# OPA847.net
KiCad netlist of a schematic drawn in Altium Designer
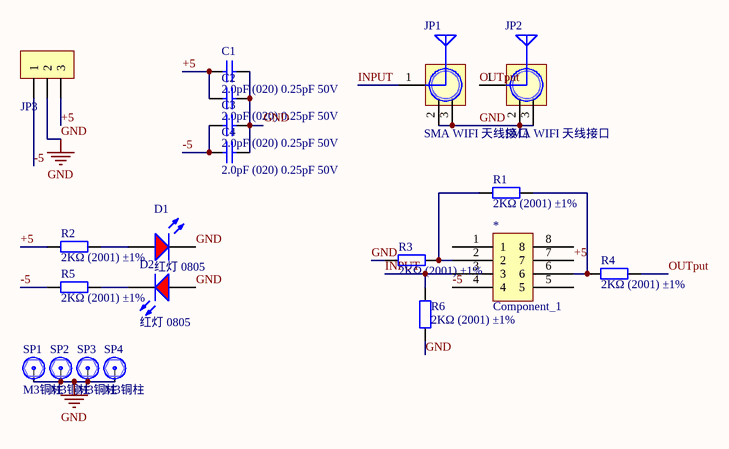
[diagram p0: OPA847.SchDoc]

(export (version "E")
  (design (tool "Eeschema 10.0.6"))
  (components
    (comp (ref "*")
      (value "Component_1")
      (footprint "SOP8_N")
      (libsource (lib "Schlib1") (part "Component_1"))
    )
    (comp (ref "C1")
      (value "2.0pF (020) 0.25pF 50V")
      (footprint "0603_C")
      (description "贴片电容")
      (libsource (lib "Miscellaneous Devices LC") (part "0603 2.0pF (020) 0.25pF 50V"))
    )
    (comp (ref "C2")
      (value "2.0pF (020) 0.25pF 50V")
      (footprint "0603_C")
      (description "贴片电容")
      (libsource (lib "Miscellaneous Devices LC") (part "0603 2.0pF (020) 0.25pF 50V"))
    )
    (comp (ref "C3")
      (value "2.0pF (020) 0.25pF 50V")
      (footprint "0603_C")
      (description "贴片电容")
      (libsource (lib "Miscellaneous Devices LC") (part "0603 2.0pF (020) 0.25pF 50V"))
    )
    (comp (ref "C4")
      (value "2.0pF (020) 0.25pF 50V")
      (footprint "0603_C")
      (description "贴片电容")
      (libsource (lib "Miscellaneous Devices LC") (part "0603 2.0pF (020) 0.25pF 50V"))
    )
    (comp (ref "D1")
      (value "红灯 0805")
      (footprint "0805_LED_S1")
      (description "发光二极管")
      (libsource (lib "Miscellaneous Devices LC") (part "0805 红灯"))
    )
    (comp (ref "D2")
      (value "红灯 0805")
      (footprint "0805_LED_S1")
      (description "发光二极管")
      (libsource (lib "Miscellaneous Devices LC") (part "0805 红灯"))
    )
    (comp (ref "JP1")
      (value "SMA WIFI 天线接口")
      (footprint "SMA-KE")
      (description "SMA-2.4G射频天线接口")
      (libsource (lib "天线") (part "SMA"))
    )
    (comp (ref "JP2")
      (value "SMA WIFI 天线接口")
      (footprint "SMA-KE")
      (description "SMA-2.4G射频天线接口")
      (libsource (lib "天线") (part "SMA"))
    )
    (comp (ref "JP3")
      (value "HDR-1X3")
      (footprint "XH2.54-WI-3P")
      (description "3P接插件")
      (libsource (lib "XH2.54") (part "Header 3"))
    )
    (comp (ref "R1")
      (value "2KΩ (2001) ±1%")
      (footprint "0805_R")
      (description "贴片电阻")
      (libsource (lib "Miscellaneous Devices LC") (part "0805 2KΩ (2001) 1%"))
    )
    (comp (ref "R2")
      (value "2KΩ (2001) ±1%")
      (footprint "0805_R")
      (description "贴片电阻")
      (libsource (lib "Miscellaneous Devices LC") (part "0805 2KΩ (2001) 1%"))
    )
    (comp (ref "R3")
      (value "2KΩ (2001) ±1%")
      (footprint "0805_R")
      (description "贴片电阻")
      (libsource (lib "Miscellaneous Devices LC") (part "0805 2KΩ (2001) 1%"))
    )
    (comp (ref "R4")
      (value "2KΩ (2001) ±1%")
      (footprint "0805_R")
      (description "贴片电阻")
      (libsource (lib "Miscellaneous Devices LC") (part "0805 2KΩ (2001) 1%"))
    )
    (comp (ref "R5")
      (value "2KΩ (2001) ±1%")
      (footprint "0805_R")
      (description "贴片电阻")
      (libsource (lib "Miscellaneous Devices LC") (part "0805 2KΩ (2001) 1%"))
    )
    (comp (ref "R6")
      (value "2KΩ (2001) ±1%")
      (footprint "0805_R")
      (description "贴片电阻")
      (libsource (lib "") (part "0805 2KΩ (2001) 1%_1"))
    )
    (comp (ref "SP1")
      (value "M3铜柱")
      (footprint "M3x4_L")
      (description "铜柱")
      (libsource (lib "铜柱-测试点-电池座-蜂鸣器") (part "铜柱小焊盘"))
    )
    (comp (ref "SP2")
      (value "M3铜柱")
      (footprint "M3x4_L")
      (description "铜柱")
      (libsource (lib "铜柱-测试点-电池座-蜂鸣器") (part "铜柱小焊盘"))
    )
    (comp (ref "SP3")
      (value "M3铜柱")
      (footprint "M3x4_L")
      (description "铜柱")
      (libsource (lib "铜柱-测试点-电池座-蜂鸣器") (part "铜柱小焊盘"))
    )
    (comp (ref "SP4")
      (value "M3铜柱")
      (footprint "M3x4_L")
      (description "铜柱")
      (libsource (lib "铜柱-测试点-电池座-蜂鸣器") (part "铜柱小焊盘"))
    )
  )
  (nets
    (net (code "1") (name "/+5") (class "Default")
      (node (ref "*") (pin "7") (pinfunction "7_7") (pintype "passive"))
      (node (ref "C1") (pin "1") (pinfunction "1_1") (pintype "passive"))
      (node (ref "C2") (pin "1") (pinfunction "1_1") (pintype "passive"))
      (node (ref "JP3") (pin "3") (pinfunction "3_3") (pintype "passive"))
      (node (ref "R2") (pin "1") (pinfunction "1_1") (pintype "passive"))
    )
    (net (code "2") (name "/-5") (class "Default")
      (node (ref "*") (pin "4") (pinfunction "4_4") (pintype "passive"))
      (node (ref "C3") (pin "1") (pinfunction "1_1") (pintype "passive"))
      (node (ref "C4") (pin "1") (pinfunction "1_1") (pintype "passive"))
      (node (ref "JP3") (pin "1") (pinfunction "1_1") (pintype "passive"))
      (node (ref "R5") (pin "1") (pinfunction "1_1") (pintype "passive"))
    )
    (net (code "3") (name "/INPUT") (class "Default")
      (node (ref "*") (pin "3") (pinfunction "3_3") (pintype "passive"))
      (node (ref "JP1") (pin "1") (pinfunction "ANT_1") (pintype "passive"))
      (node (ref "R6") (pin "2") (pinfunction "2_2") (pintype "passive"))
    )
    (net (code "4") (name "/OUTput") (class "Default")
      (node (ref "JP2") (pin "1") (pinfunction "ANT_1") (pintype "passive"))
      (node (ref "R4") (pin "2") (pinfunction "2_2") (pintype "passive"))
    )
    (net (code "5") (name "GND") (class "Default")
      (node (ref "C1") (pin "2") (pinfunction "2_2") (pintype "passive"))
      (node (ref "C2") (pin "2") (pinfunction "2_2") (pintype "passive"))
      (node (ref "C3") (pin "2") (pinfunction "2_2") (pintype "passive"))
      (node (ref "C4") (pin "2") (pinfunction "2_2") (pintype "passive"))
      (node (ref "D1") (pin "K") (pinfunction "K_K") (pintype "passive"))
      (node (ref "D2") (pin "A") (pinfunction "A_A") (pintype "passive"))
      (node (ref "JP1") (pin "2") (pinfunction "GND_2") (pintype "passive"))
      (node (ref "JP1") (pin "3") (pinfunction "GND_3") (pintype "passive"))
      (node (ref "JP2") (pin "2") (pinfunction "GND_2") (pintype "passive"))
      (node (ref "JP2") (pin "3") (pinfunction "GND_3") (pintype "passive"))
      (node (ref "JP3") (pin "2") (pinfunction "2_2") (pintype "passive"))
      (node (ref "R3") (pin "1") (pinfunction "1_1") (pintype "passive"))
      (node (ref "R6") (pin "1") (pinfunction "1_1") (pintype "passive"))
      (node (ref "SP1") (pin "1") (pinfunction "1_1") (pintype "passive"))
      (node (ref "SP2") (pin "1") (pinfunction "1_1") (pintype "passive"))
      (node (ref "SP3") (pin "1") (pinfunction "1_1") (pintype "passive"))
      (node (ref "SP4") (pin "1") (pinfunction "1_1") (pintype "passive"))
    )
    (net (code "6") (name "Net-(*-Pad2)") (class "Default")
      (node (ref "*") (pin "2") (pinfunction "2_2") (pintype "passive"))
      (node (ref "R1") (pin "1") (pinfunction "1_1") (pintype "passive"))
      (node (ref "R3") (pin "2") (pinfunction "2_2") (pintype "passive"))
    )
    (net (code "7") (name "Net-(*-Pad6)") (class "Default")
      (node (ref "*") (pin "6") (pinfunction "6_6") (pintype "passive"))
      (node (ref "R1") (pin "2") (pinfunction "2_2") (pintype "passive"))
      (node (ref "R4") (pin "1") (pinfunction "1_1") (pintype "passive"))
    )
    (net (code "8") (name "Net-(D1-PadA)") (class "Default")
      (node (ref "D1") (pin "A") (pinfunction "A_A") (pintype "passive"))
      (node (ref "R2") (pin "2") (pinfunction "2_2") (pintype "passive"))
    )
    (net (code "9") (name "Net-(D2-PadK)") (class "Default")
      (node (ref "D2") (pin "K") (pinfunction "K_K") (pintype "passive"))
      (node (ref "R5") (pin "2") (pinfunction "2_2") (pintype "passive"))
    )
    (net (code "10") (name "unconnected-(*-Pad1)") (class "Default")
      (node (ref "*") (pin "1") (pinfunction "1_1") (pintype "passive"))
    )
    (net (code "11") (name "unconnected-(*-Pad5)") (class "Default")
      (node (ref "*") (pin "5") (pinfunction "5_5") (pintype "passive"))
    )
    (net (code "12") (name "unconnected-(*-Pad8)") (class "Default")
      (node (ref "*") (pin "8") (pinfunction "8_8") (pintype "passive"))
    )
  )
)
